# LM399.net
KiCad netlist of a schematic drawn in Altium Designer
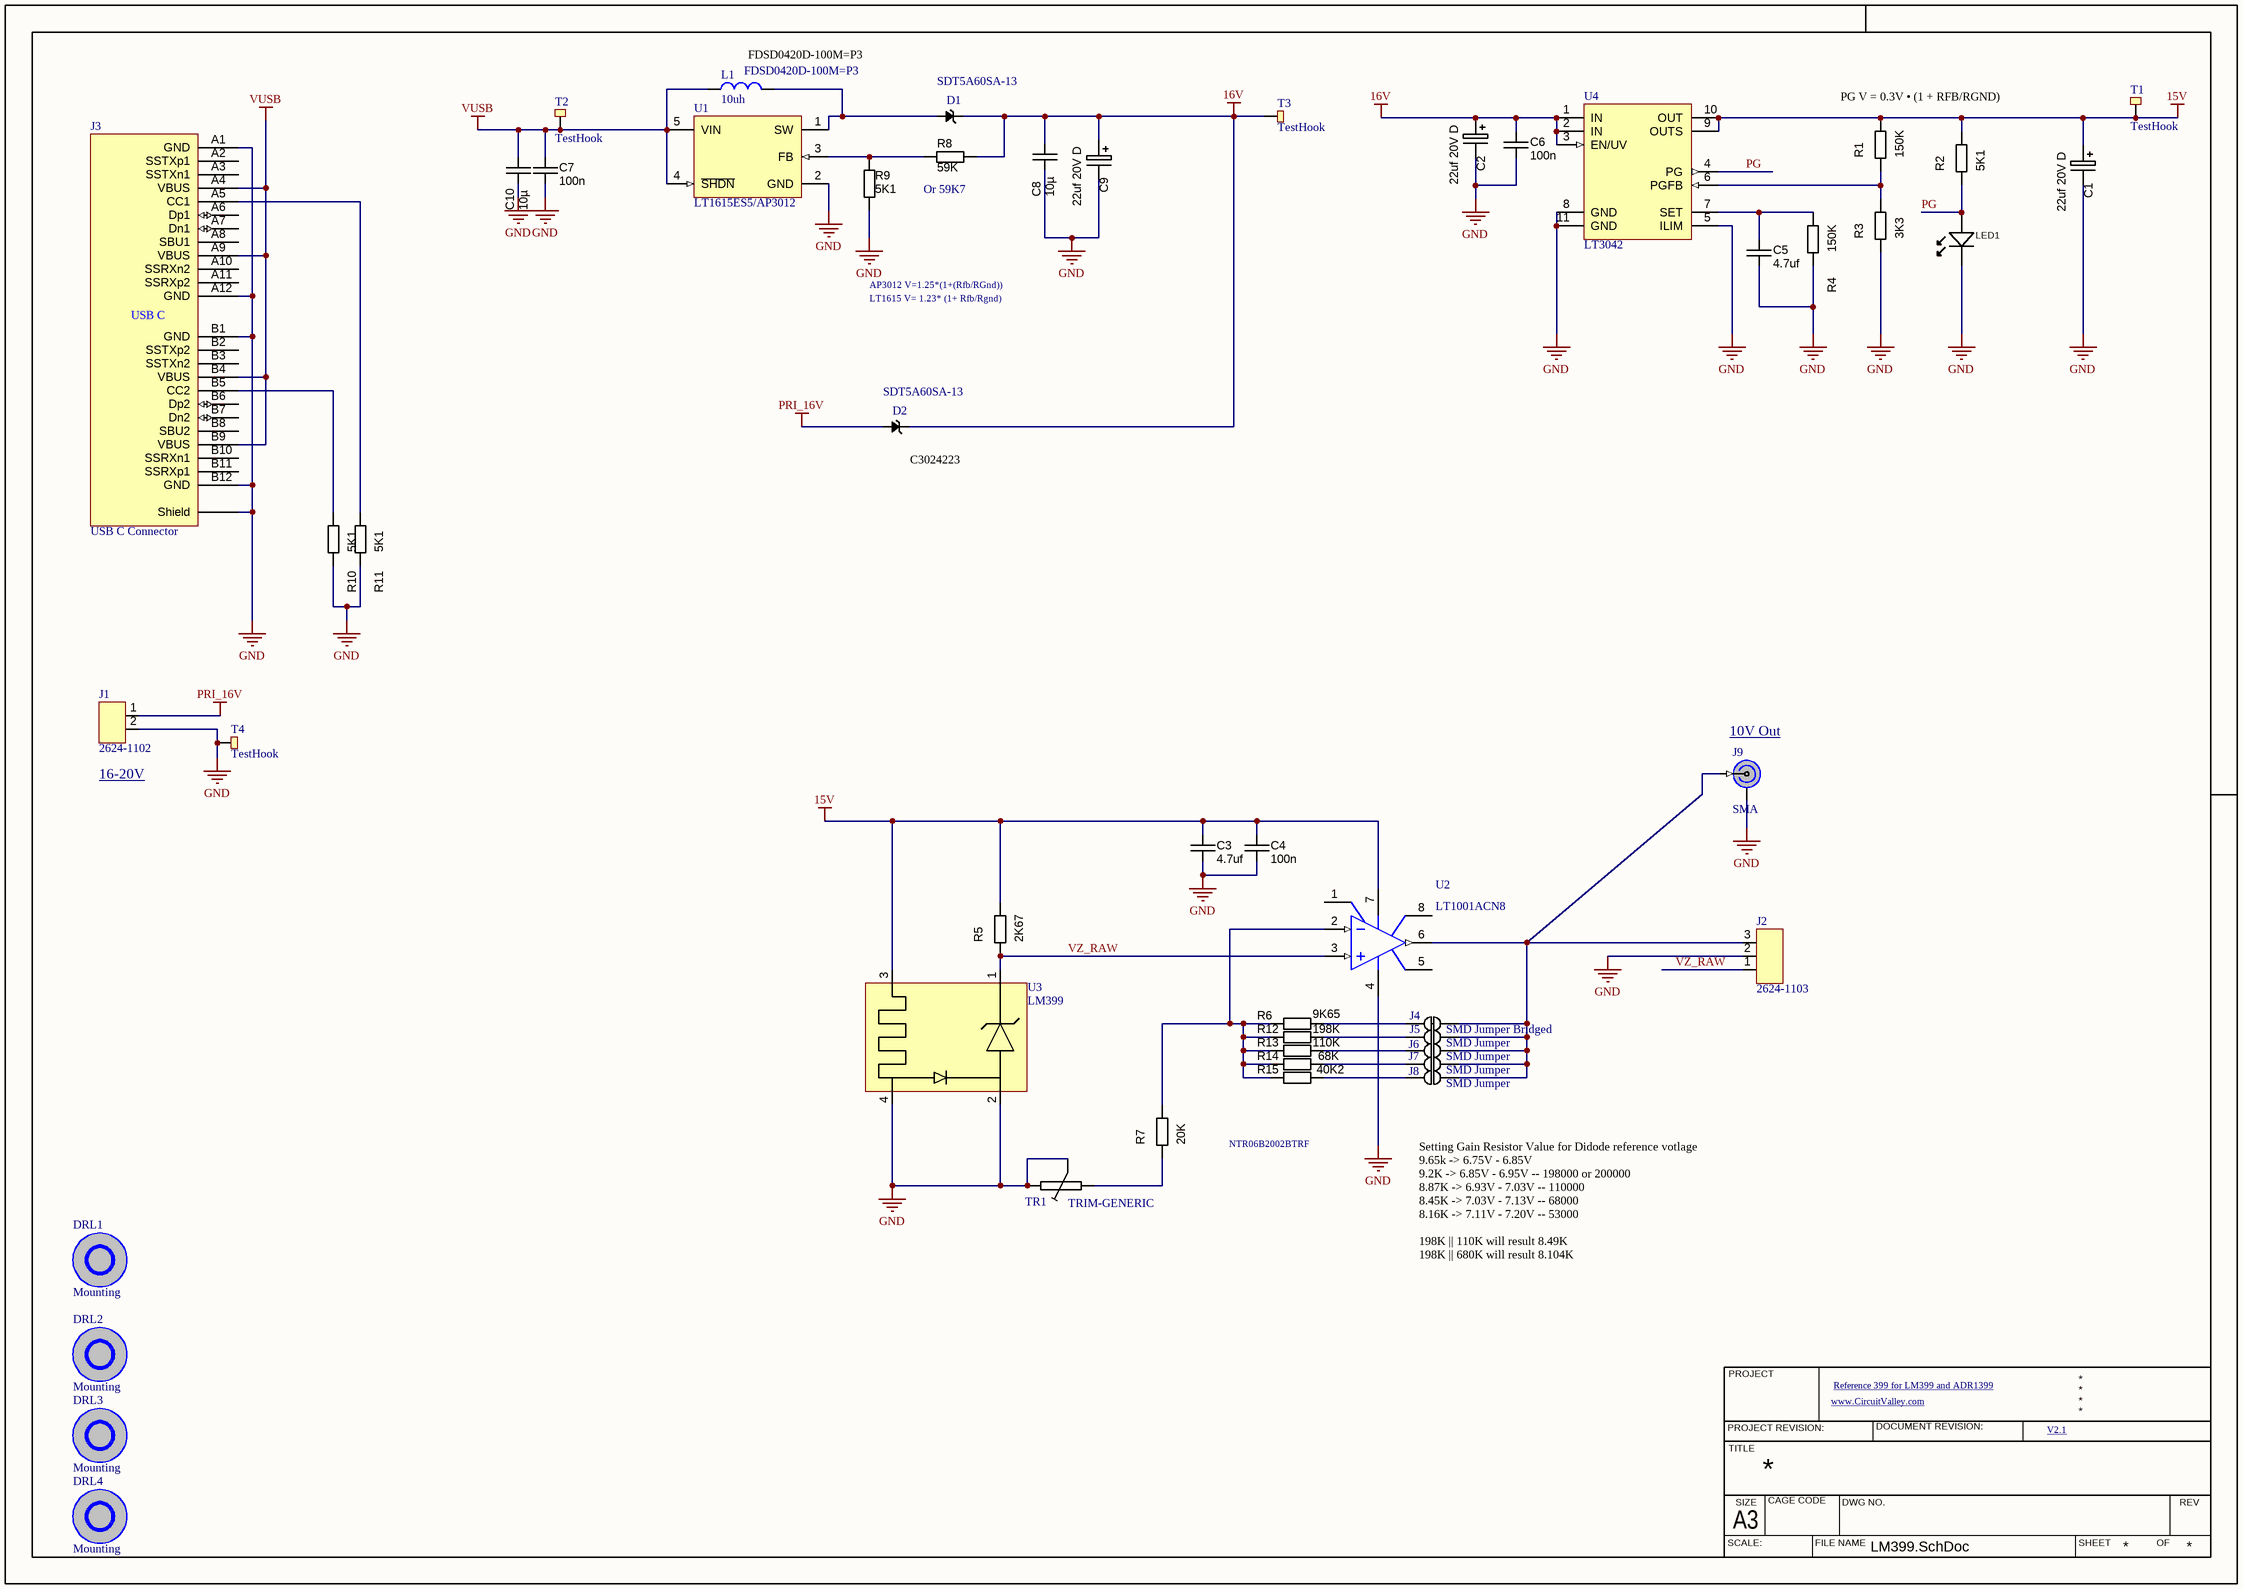
[diagram p0: LM399.SchDoc]

(export (version "E")
  (design (tool "Eeschema 10.0.6"))
  (components
    (comp (ref "C1")
      (value "22uf 20V D")
      (footprint "CAPMP7343X310N")
      (description "Capacitor SMD Tant 330uF 20% 6V3 2917")
      (fields
        (field (name "TOLERANCE") "±20%")
        (field (name "MANUFACTURER PART NUMBER") "T520D337M006ATE015")
      )
      (libsource (lib "PBL - Capacitors") (part "CAPT_330u_2917_6V3"))
    )
    (comp (ref "C2")
      (value "22uf 20V D")
      (footprint "CAPMP7343X310N")
      (description "Capacitor SMD Tant 330uF 20% 6V3 2917")
      (fields
        (field (name "TOLERANCE") "±20%")
        (field (name "MANUFACTURER PART NUMBER") "T520D337M006ATE015")
      )
      (libsource (lib "PBL - Capacitors") (part "CAPT_330u_2917_6V3"))
    )
    (comp (ref "C3")
      (value "4.7uf")
      (footprint "CAPC1608N")
      (description "Capacitor SMD Cer 1nF 10% 100V X7R 0603")
      (fields (field (name "TOLERANCE") "±10%") (field (name "Comment") "approved sub OK"))
      (libsource (lib "PBL - Capacitors") (part "CAPC_1n_0603_100V"))
    )
    (comp (ref "C4")
      (value "100n")
      (footprint "CAPC1608N")
      (description "Capacitor SMD Cer 1nF 10% 100V X7R 0603")
      (fields (field (name "TOLERANCE") "±10%") (field (name "Comment") "approved sub OK"))
      (libsource (lib "PBL - Capacitors") (part "CAPC_1n_0603_100V"))
    )
    (comp (ref "C5")
      (value "4.7uf")
      (footprint "CAPC1608N")
      (description "Capacitor SMD Cer 1nF 10% 100V X7R 0603")
      (fields (field (name "TOLERANCE") "±10%") (field (name "Comment") "approved sub OK"))
      (libsource (lib "PBL - Capacitors") (part "CAPC_1n_0603_100V"))
    )
    (comp (ref "C6")
      (value "100n")
      (footprint "CAPC1608N")
      (description "Capacitor SMD Cer 1nF 10% 100V X7R 0603")
      (fields (field (name "TOLERANCE") "±10%") (field (name "Comment") "approved sub OK"))
      (libsource (lib "PBL - Capacitors") (part "CAPC_1n_0603_100V"))
    )
    (comp (ref "C7")
      (value "100n")
      (footprint "CAPC1608N")
      (description "Capacitor SMD Cer 1nF 10% 100V X7R 0603")
      (fields (field (name "TOLERANCE") "±10%") (field (name "Comment") "approved sub OK"))
      (libsource (lib "PBL - Capacitors") (part "CAPC_1n_0603_100V"))
    )
    (comp (ref "C8")
      (value "10µ")
      (footprint "CAPC3225N")
      (description "Capacitor SMD Cer 10uF 20% 16V X5R 1210")
      (fields (field (name "TOLERANCE") "±20%"))
      (libsource (lib "PBL - Capacitors") (part "CAPC_10u_1210_50V"))
    )
    (comp (ref "C9")
      (value "22uf 20V D")
      (footprint "CAPMP7343X310N")
      (description "Capacitor SMD Tant 330uF 20% 6V3 2917")
      (fields
        (field (name "TOLERANCE") "±20%")
        (field (name "MANUFACTURER PART NUMBER") "T520D337M006ATE015")
      )
      (libsource (lib "PBL - Capacitors") (part "CAPT_330u_2917_6V3"))
    )
    (comp (ref "C10")
      (value "10µ")
      (footprint "CAPC3225N")
      (description "Capacitor SMD Cer 10uF 20% 16V X5R 1210")
      (fields (field (name "TOLERANCE") "±20%"))
      (libsource (lib "PBL - Capacitors") (part "CAPC_10u_1210_50V"))
    )
    (comp (ref "D1")
      (value "SDT5A60SA-13")
      (footprint "DO-214AC")
      (libsource (lib "cvlib") (part "Schottky_diode"))
    )
    (comp (ref "D2")
      (value "SDT5A60SA-13")
      (footprint "DO-214AC")
      (libsource (lib "cvlib") (part "Schottky_diode"))
    )
    (comp (ref "DRL1")
      (value "Mounting")
      (footprint "NO_COPPER_NOMASK_2m75_6m2")
      (description "Mounting Hole")
      (libsource (lib "cvlib") (part "Mountinghole"))
    )
    (comp (ref "DRL2")
      (value "Mounting")
      (footprint "NO_COPPER_NOMASK_2m75_6m2")
      (description "Mounting Hole")
      (libsource (lib "cvlib") (part "Mountinghole"))
    )
    (comp (ref "DRL3")
      (value "Mounting")
      (footprint "NO_COPPER_NOMASK_2m75_6m2")
      (description "Mounting Hole")
      (libsource (lib "cvlib") (part "Mountinghole"))
    )
    (comp (ref "DRL4")
      (value "Mounting")
      (footprint "NO_COPPER_NOMASK_2m75_6m2")
      (description "Mounting Hole")
      (libsource (lib "cvlib") (part "Mountinghole"))
    )
    (comp (ref "J1") (value "2624-1102") (footprint "2624-1102") (libsource (lib "cvlib") (part "2624-1102")))
    (comp (ref "J2") (value "2624-1103") (footprint "2624-1103") (libsource (lib "cvlib") (part "2624-1103")))
    (comp (ref "J3")
      (value "USB C Connector")
      (footprint "UT11113-11602-7H")
      (description "USB C connector")
      (libsource (lib "cvlib") (part "USB_C"))
    )
    (comp (ref "J4")
      (value "SMD Jumper Bridged")
      (footprint "SMD_Jumper_bridge")
      (description "SMD Jumper")
      (libsource (lib "cvlib") (part "SMD_Jumper_Bridged"))
    )
    (comp (ref "J5")
      (value "SMD Jumper")
      (footprint "SMD_Jumper")
      (libsource (lib "cvlib") (part "SMD_Jumper"))
    )
    (comp (ref "J6")
      (value "SMD Jumper")
      (footprint "SMD_Jumper")
      (libsource (lib "cvlib") (part "SMD_Jumper"))
    )
    (comp (ref "J7")
      (value "SMD Jumper")
      (footprint "SMD_Jumper")
      (libsource (lib "cvlib") (part "SMD_Jumper"))
    )
    (comp (ref "J8")
      (value "SMD Jumper")
      (footprint "SMD_Jumper")
      (libsource (lib "cvlib") (part "SMD_Jumper"))
    )
    (comp (ref "J9")
      (value "SMA")
      (footprint "SMA_Connector")
      (libsource (lib "cvlib") (part "SMA Connector"))
    )
    (comp (ref "L1")
      (value "10uh")
      (footprint "FDSD0420-H-2R2M")
      (fields (field (name "ALTIUM_VALUE") "FDSD0420D-100M=P3"))
      (libsource (lib "cvlib") (part "inductor_smd"))
    )
    (comp (ref "LED1")
      (value "~")
      (footprint "LED-0805-K")
      (description "LED, 0805 SMD, Green")
      (libsource (lib "PBL - Light Sources") (part "LED_SMD_Green_0805"))
    )
    (comp (ref "R1")
      (value "150K")
      (footprint "RESC1608N")
      (description "Resistor, SMD chip")
      (fields (field (name "TOLERANCE") "±5%") (field (name "Comment") "RES_NL_0603"))
      (libsource (lib "") (part "RES_NL_0603_1"))
    )
    (comp (ref "R2")
      (value "5K1")
      (footprint "RESC1608N")
      (description "Resistor, SMD chip")
      (fields (field (name "TOLERANCE") "±5%") (field (name "Comment") "RES_NL_0603"))
      (libsource (lib "") (part "RES_NL_0603_1"))
    )
    (comp (ref "R3")
      (value "3K3")
      (footprint "RESC1608N")
      (description "Resistor, SMD chip")
      (fields (field (name "TOLERANCE") "±5%") (field (name "Comment") "RES_NL_0603"))
      (libsource (lib "") (part "RES_NL_0603_1"))
    )
    (comp (ref "R4")
      (value "150K")
      (footprint "RESC1608N")
      (description "Resistor, SMD chip")
      (fields (field (name "TOLERANCE") "±5%") (field (name "Comment") "RES_NL_0603"))
      (libsource (lib "") (part "RES_NL_0603_1"))
    )
    (comp (ref "R5")
      (value "2K67")
      (footprint "RESC1608N")
      (description "Resistor, SMD chip")
      (fields (field (name "TOLERANCE") "±5%") (field (name "Comment") "RES_NL_0603"))
      (libsource (lib "") (part "RES_NL_0603_1"))
    )
    (comp (ref "R6")
      (value "9K65")
      (footprint "RESC1608N")
      (description "Resistor, SMD chip")
      (fields (field (name "TOLERANCE") "±5%") (field (name "Comment") "RES_NL_0603"))
      (libsource (lib "PBL - Resistors") (part "RES_NL_0603"))
    )
    (comp (ref "R7")
      (value "20K")
      (footprint "RESC1608N")
      (description "Resistor, SMD chip")
      (fields (field (name "TOLERANCE") "±5%") (field (name "Comment") "RES_NL_0603"))
      (libsource (lib "") (part "RES_NL_0603_1"))
    )
    (comp (ref "R8")
      (value "59K")
      (footprint "RESC1608N")
      (description "Resistor, SMD chip")
      (fields (field (name "TOLERANCE") "±5%") (field (name "Comment") "RES_NL_0603"))
      (libsource (lib "PBL - Resistors") (part "RES_NL_0603"))
    )
    (comp (ref "R9")
      (value "5K1")
      (footprint "RESC1608N")
      (description "Resistor, SMD chip")
      (fields (field (name "TOLERANCE") "±5%") (field (name "Comment") "RES_NL_0603"))
      (libsource (lib "") (part "RES_NL_0603_2"))
    )
    (comp (ref "R10")
      (value "5K1")
      (footprint "RESC1608N")
      (description "Resistor, SMD chip")
      (fields (field (name "TOLERANCE") "±5%") (field (name "Comment") "RES_NL_0603"))
      (libsource (lib "") (part "RES_NL_0603_1"))
    )
    (comp (ref "R11")
      (value "5K1")
      (footprint "RESC1608N")
      (description "Resistor, SMD chip")
      (fields (field (name "TOLERANCE") "±5%") (field (name "Comment") "RES_NL_0603"))
      (libsource (lib "") (part "RES_NL_0603_1"))
    )
    (comp (ref "R12")
      (value "198K")
      (footprint "RESC1608N")
      (description "Resistor, SMD chip")
      (fields (field (name "TOLERANCE") "±5%") (field (name "Comment") "RES_NL_0603"))
      (libsource (lib "PBL - Resistors") (part "RES_NL_0603"))
    )
    (comp (ref "R13")
      (value "110K")
      (footprint "RESC1608N")
      (description "Resistor, SMD chip")
      (fields (field (name "TOLERANCE") "±5%") (field (name "Comment") "RES_NL_0603"))
      (libsource (lib "PBL - Resistors") (part "RES_NL_0603"))
    )
    (comp (ref "R14")
      (value "68K")
      (footprint "RESC1608N")
      (description "Resistor, SMD chip")
      (fields (field (name "TOLERANCE") "±5%") (field (name "Comment") "RES_NL_0603"))
      (libsource (lib "PBL - Resistors") (part "RES_NL_0603"))
    )
    (comp (ref "R15")
      (value "40K2")
      (footprint "RESC1608N")
      (description "Resistor, SMD chip")
      (fields (field (name "TOLERANCE") "±5%") (field (name "Comment") "RES_NL_0603"))
      (libsource (lib "PBL - Resistors") (part "RES_NL_0603"))
    )
    (comp (ref "T1")
      (value "TestHook")
      (footprint "TEST_PAD_HOOK")
      (libsource (lib "cvlib") (part "TestHook"))
    )
    (comp (ref "T2")
      (value "TestHook")
      (footprint "TEST_PAD_HOOK")
      (libsource (lib "cvlib") (part "TestHook"))
    )
    (comp (ref "T3") (value "TestHook") (footprint "TEST_PAD_HOOK") (libsource (lib "") (part "TestHook_1")))
    (comp (ref "T4") (value "TestHook") (footprint "TEST_PAD_HOOK") (libsource (lib "") (part "TestHook_1")))
    (comp (ref "TR1")
      (value "TRIM-GENERIC")
      (footprint "TRIMMER-MT")
      (description "TRIMMABLE RESISTOR")
      (libsource (lib "Generic") (part "THTRIM-GENERIC"))
    )
    (comp (ref "U1")
      (value "LT1615ES5/AP3012")
      (footprint "SOT23-5")
      (description "Boost Conveter")
      (libsource (lib "cvlib") (part "AP3012"))
    )
    (comp (ref "U2")
      (value "LT1001ACN8")
      (footprint "N8")
      (description "General Purpose, High Precision Op Amp")
      (fields (field (name "PUBLISHER") "Altium Limited"))
      (libsource (lib "LT Operational Amplifier") (part "LT1001ACN8"))
    )
    (comp (ref "U3") (value "LM399") (footprint "TO-46") (libsource (lib "cvlib") (part "LM399")))
    (comp (ref "U4")
      (value "LT3042")
      (footprint "MSOP10")
      (description "Low noise Linear Regulator")
      (libsource (lib "cvlib") (part "LT3042"))
    )
  )
  (nets
    (net (code "1") (name "/PG") (class "Default")
      (node (ref "LED1") (pin "A") (pinfunction "A_A") (pintype "passive"))
      (node (ref "R2") (pin "2") (pinfunction "2_2") (pintype "passive"))
      (node (ref "U4") (pin "4") (pinfunction "PG_4") (pintype "output"))
    )
    (net (code "2") (name "/VZ_RAW") (class "Default")
      (node (ref "J2") (pin "1") (pintype "passive"))
      (node (ref "R5") (pin "2") (pinfunction "2_2") (pintype "passive"))
      (node (ref "U2") (pin "3") (pinfunction "IN+_3") (pintype "input"))
      (node (ref "U3") (pin "1") (pinfunction "D1_1") (pintype "passive"))
    )
    (net (code "3") (name "15V") (class "Default")
      (node (ref "C1") (pin "1") (pintype "passive"))
      (node (ref "C3") (pin "1") (pintype "passive"))
      (node (ref "C4") (pin "1") (pintype "passive"))
      (node (ref "R1") (pin "1") (pinfunction "1_1") (pintype "passive"))
      (node (ref "R2") (pin "1") (pinfunction "1_1") (pintype "passive"))
      (node (ref "R5") (pin "1") (pinfunction "1_1") (pintype "passive"))
      (node (ref "T1") (pin "1") (pinfunction "TP_1") (pintype "power_in"))
      (node (ref "U2") (pin "7") (pinfunction "V+_7") (pintype "power_in"))
      (node (ref "U3") (pin "3") (pinfunction "H1_3") (pintype "passive"))
      (node (ref "U4") (pin "10") (pinfunction "OUT_10") (pintype "power_in"))
      (node (ref "U4") (pin "9") (pinfunction "OUTS_9") (pintype "passive"))
    )
    (net (code "4") (name "16V") (class "Default")
      (node (ref "C2") (pin "1") (pintype "passive"))
      (node (ref "C6") (pin "1") (pintype "passive"))
      (node (ref "C8") (pin "1") (pintype "passive"))
      (node (ref "C9") (pin "1") (pintype "passive"))
      (node (ref "D1") (pin "2") (pinfunction "2_2") (pintype "passive"))
      (node (ref "D2") (pin "2") (pinfunction "2_2") (pintype "passive"))
      (node (ref "R8") (pin "2") (pinfunction "2_2") (pintype "passive"))
      (node (ref "T3") (pin "1") (pinfunction "TP_1") (pintype "power_in"))
      (node (ref "U4") (pin "1") (pinfunction "IN_1") (pintype "power_in"))
      (node (ref "U4") (pin "2") (pinfunction "IN_2") (pintype "power_in"))
      (node (ref "U4") (pin "3") (pinfunction "EN/UV_3") (pintype "input"))
    )
    (net (code "5") (name "GND") (class "Default")
      (node (ref "C1") (pin "2") (pintype "passive"))
      (node (ref "C10") (pin "2") (pintype "passive"))
      (node (ref "C2") (pin "2") (pintype "passive"))
      (node (ref "C3") (pin "2") (pintype "passive"))
      (node (ref "C4") (pin "2") (pintype "passive"))
      (node (ref "C5") (pin "2") (pintype "passive"))
      (node (ref "C6") (pin "2") (pintype "passive"))
      (node (ref "C7") (pin "2") (pintype "passive"))
      (node (ref "C8") (pin "2") (pintype "passive"))
      (node (ref "C9") (pin "2") (pintype "passive"))
      (node (ref "J1") (pin "2") (pinfunction "PW_2") (pintype "passive"))
      (node (ref "J2") (pin "2") (pintype "passive"))
      (node (ref "J3") (pin "0") (pinfunction "Shield_0") (pintype "power_in"))
      (node (ref "J3") (pin "A1") (pinfunction "GND_A1") (pintype "power_in"))
      (node (ref "J3") (pin "A12") (pinfunction "GND_A12") (pintype "power_in"))
      (node (ref "J3") (pin "B1") (pinfunction "GND_B1") (pintype "power_in"))
      (node (ref "J3") (pin "B12") (pinfunction "GND_B12") (pintype "power_in"))
      (node (ref "J9") (pin "2") (pinfunction "2_2") (pintype "passive"))
      (node (ref "LED1") (pin "K") (pinfunction "K_K") (pintype "passive"))
      (node (ref "R10") (pin "2") (pinfunction "2_2") (pintype "passive"))
      (node (ref "R11") (pin "2") (pinfunction "2_2") (pintype "passive"))
      (node (ref "R3") (pin "2") (pinfunction "2_2") (pintype "passive"))
      (node (ref "R4") (pin "2") (pinfunction "2_2") (pintype "passive"))
      (node (ref "R9") (pin "1") (pinfunction "1_1") (pintype "passive"))
      (node (ref "T4") (pin "1") (pinfunction "TP_1") (pintype "power_in"))
      (node (ref "TR1") (pin "2") (pinfunction "2_2") (pintype "passive"))
      (node (ref "TR1") (pin "W") (pinfunction "W_W") (pintype "passive"))
      (node (ref "U1") (pin "2") (pinfunction "GND_2") (pintype "power_in"))
      (node (ref "U2") (pin "4") (pinfunction "V-_4") (pintype "power_in"))
      (node (ref "U3") (pin "2") (pinfunction "D2_2") (pintype "passive"))
      (node (ref "U3") (pin "4") (pinfunction "H2_4") (pintype "passive"))
      (node (ref "U4") (pin "11") (pinfunction "GND_11") (pintype "passive"))
      (node (ref "U4") (pin "5") (pinfunction "ILIM_5") (pintype "passive"))
      (node (ref "U4") (pin "8") (pinfunction "GND_8") (pintype "passive"))
    )
    (net (code "6") (name "Net-(J3-CC1)") (class "Default")
      (node (ref "J3") (pin "A5") (pinfunction "CC1_A5") (pintype "power_in"))
      (node (ref "R11") (pin "1") (pinfunction "1_1") (pintype "passive"))
    )
    (net (code "7") (name "Net-(J3-CC2)") (class "Default")
      (node (ref "J3") (pin "B5") (pinfunction "CC2_B5") (pintype "power_in"))
      (node (ref "R10") (pin "1") (pinfunction "1_1") (pintype "passive"))
    )
    (net (code "8") (name "Net-(J4-Pad2)") (class "Default")
      (node (ref "J4") (pin "2") (pinfunction "2_2") (pintype "passive"))
      (node (ref "R6") (pin "2") (pinfunction "2_2") (pintype "passive"))
    )
    (net (code "9") (name "Net-(J5-Pad2)") (class "Default")
      (node (ref "J5") (pin "2") (pinfunction "2_2") (pintype "passive"))
      (node (ref "R12") (pin "2") (pinfunction "2_2") (pintype "passive"))
    )
    (net (code "10") (name "Net-(J6-Pad2)") (class "Default")
      (node (ref "J6") (pin "2") (pinfunction "2_2") (pintype "passive"))
      (node (ref "R13") (pin "2") (pinfunction "2_2") (pintype "passive"))
    )
    (net (code "11") (name "Net-(J7-Pad2)") (class "Default")
      (node (ref "J7") (pin "2") (pinfunction "2_2") (pintype "passive"))
      (node (ref "R14") (pin "2") (pinfunction "2_2") (pintype "passive"))
    )
    (net (code "12") (name "Net-(J8-Pad2)") (class "Default")
      (node (ref "J8") (pin "2") (pinfunction "2_2") (pintype "passive"))
      (node (ref "R15") (pin "2") (pinfunction "2_2") (pintype "passive"))
    )
    (net (code "13") (name "Net-(R7-Pad2)") (class "Default")
      (node (ref "R7") (pin "2") (pinfunction "2_2") (pintype "passive"))
      (node (ref "TR1") (pin "1") (pinfunction "1_1") (pintype "passive"))
    )
    (net (code "14") (name "Net-(U1-FB)") (class "Default")
      (node (ref "R8") (pin "1") (pinfunction "1_1") (pintype "passive"))
      (node (ref "R9") (pin "2") (pinfunction "2_2") (pintype "passive"))
      (node (ref "U1") (pin "3") (pinfunction "FB_3") (pintype "input"))
    )
    (net (code "15") (name "Net-(U1-SW)") (class "Default")
      (node (ref "D1") (pin "1") (pinfunction "1_1") (pintype "passive"))
      (node (ref "L1") (pin "2") (pinfunction "2_2") (pintype "passive"))
      (node (ref "U1") (pin "1") (pinfunction "SW_1") (pintype "power_in"))
    )
    (net (code "16") (name "Net-(U2-IN-)") (class "Default")
      (node (ref "R12") (pin "1") (pinfunction "1_1") (pintype "passive"))
      (node (ref "R13") (pin "1") (pinfunction "1_1") (pintype "passive"))
      (node (ref "R14") (pin "1") (pinfunction "1_1") (pintype "passive"))
      (node (ref "R15") (pin "1") (pinfunction "1_1") (pintype "passive"))
      (node (ref "R6") (pin "1") (pinfunction "1_1") (pintype "passive"))
      (node (ref "R7") (pin "1") (pinfunction "1_1") (pintype "passive"))
      (node (ref "U2") (pin "2") (pinfunction "IN-_2") (pintype "input"))
    )
    (net (code "17") (name "Net-(U2-OUT)") (class "Default")
      (node (ref "J2") (pin "3") (pintype "passive"))
      (node (ref "J4") (pin "1") (pinfunction "1_1") (pintype "passive"))
      (node (ref "J5") (pin "1") (pinfunction "1_1") (pintype "passive"))
      (node (ref "J6") (pin "1") (pinfunction "1_1") (pintype "passive"))
      (node (ref "J7") (pin "1") (pinfunction "1_1") (pintype "passive"))
      (node (ref "J8") (pin "1") (pinfunction "1_1") (pintype "passive"))
      (node (ref "J9") (pin "1") (pinfunction "1_1") (pintype "input"))
      (node (ref "U2") (pin "6") (pinfunction "OUT_6") (pintype "output"))
    )
    (net (code "18") (name "Net-(U4-PGFB)") (class "Default")
      (node (ref "R1") (pin "2") (pinfunction "2_2") (pintype "passive"))
      (node (ref "R3") (pin "1") (pinfunction "1_1") (pintype "passive"))
      (node (ref "U4") (pin "6") (pinfunction "PGFB_6") (pintype "input"))
    )
    (net (code "19") (name "Net-(U4-SET)") (class "Default")
      (node (ref "C5") (pin "1") (pintype "passive"))
      (node (ref "R4") (pin "1") (pinfunction "1_1") (pintype "passive"))
      (node (ref "U4") (pin "7") (pinfunction "SET_7") (pintype "passive"))
    )
    (net (code "20") (name "PRI_16V") (class "Default")
      (node (ref "D2") (pin "1") (pinfunction "1_1") (pintype "passive"))
      (node (ref "J1") (pin "1") (pinfunction "PW_1") (pintype "passive"))
    )
    (net (code "21") (name "VUSB") (class "Default")
      (node (ref "C10") (pin "1") (pintype "passive"))
      (node (ref "C7") (pin "1") (pintype "passive"))
      (node (ref "J3") (pin "A4") (pinfunction "VBUS_A4") (pintype "power_in"))
      (node (ref "J3") (pin "A9") (pinfunction "VBUS_A9") (pintype "power_in"))
      (node (ref "J3") (pin "B4") (pinfunction "VBUS_B4") (pintype "power_in"))
      (node (ref "J3") (pin "B9") (pinfunction "VBUS_B9") (pintype "power_in"))
      (node (ref "L1") (pin "1") (pinfunction "1_1") (pintype "passive"))
      (node (ref "T2") (pin "1") (pinfunction "TP_1") (pintype "power_in"))
      (node (ref "U1") (pin "4") (pinfunction "~{SHDN}_4") (pintype "input"))
      (node (ref "U1") (pin "5") (pinfunction "VIN_5") (pintype "power_in"))
    )
    (net (code "22") (name "unconnected-(J3-Dn1-PadA7)") (class "Default")
      (node (ref "J3") (pin "A7") (pinfunction "Dn1_A7") (pintype "bidirectional"))
    )
    (net (code "23") (name "unconnected-(J3-Dn2-PadB7)") (class "Default")
      (node (ref "J3") (pin "B7") (pinfunction "Dn2_B7") (pintype "bidirectional"))
    )
    (net (code "24") (name "unconnected-(J3-Dp1-PadA6)") (class "Default")
      (node (ref "J3") (pin "A6") (pinfunction "Dp1_A6") (pintype "bidirectional"))
    )
    (net (code "25") (name "unconnected-(J3-Dp2-PadB6)") (class "Default")
      (node (ref "J3") (pin "B6") (pinfunction "Dp2_B6") (pintype "bidirectional"))
    )
    (net (code "26") (name "unconnected-(J3-SBU1-PadA8)") (class "Default")
      (node (ref "J3") (pin "A8") (pinfunction "SBU1_A8") (pintype "power_in"))
    )
    (net (code "27") (name "unconnected-(J3-SBU2-PadB8)") (class "Default")
      (node (ref "J3") (pin "B8") (pinfunction "SBU2_B8") (pintype "power_in"))
    )
    (net (code "28") (name "unconnected-(J3-SSRXn1-PadB10)") (class "Default")
      (node (ref "J3") (pin "B10") (pinfunction "SSRXn1_B10") (pintype "passive"))
    )
    (net (code "29") (name "unconnected-(J3-SSRXn2-PadA10)") (class "Default")
      (node (ref "J3") (pin "A10") (pinfunction "SSRXn2_A10") (pintype "passive"))
    )
    (net (code "30") (name "unconnected-(J3-SSRXp1-PadB11)") (class "Default")
      (node (ref "J3") (pin "B11") (pinfunction "SSRXp1_B11") (pintype "passive"))
    )
    (net (code "31") (name "unconnected-(J3-SSRXp2-PadA11)") (class "Default")
      (node (ref "J3") (pin "A11") (pinfunction "SSRXp2_A11") (pintype "passive"))
    )
    (net (code "32") (name "unconnected-(J3-SSTXn1-PadA3)") (class "Default")
      (node (ref "J3") (pin "A3") (pinfunction "SSTXn1_A3") (pintype "passive"))
    )
    (net (code "33") (name "unconnected-(J3-SSTXn2-PadB3)") (class "Default")
      (node (ref "J3") (pin "B3") (pinfunction "SSTXn2_B3") (pintype "passive"))
    )
    (net (code "34") (name "unconnected-(J3-SSTXp1-PadA2)") (class "Default")
      (node (ref "J3") (pin "A2") (pinfunction "SSTXp1_A2") (pintype "passive"))
    )
    (net (code "35") (name "unconnected-(J3-SSTXp2-PadB2)") (class "Default")
      (node (ref "J3") (pin "B2") (pinfunction "SSTXp2_B2") (pintype "passive"))
    )
    (net (code "36") (name "unconnected-(U2-NC-Pad5)") (class "Default")
      (node (ref "U2") (pin "5") (pinfunction "NC_5") (pintype "passive"))
    )
    (net (code "37") (name "unconnected-(U2-VOSTRIM-Pad1)") (class "Default")
      (node (ref "U2") (pin "1") (pinfunction "VOSTRIM_1") (pintype "passive"))
    )
    (net (code "38") (name "unconnected-(U2-VOSTRIM-Pad8)") (class "Default")
      (node (ref "U2") (pin "8") (pinfunction "VOSTRIM_8") (pintype "passive"))
    )
  )
)
